# openevse-ac-filter-v1_1.net
KiCad netlist of a schematic drawn in EAGLE
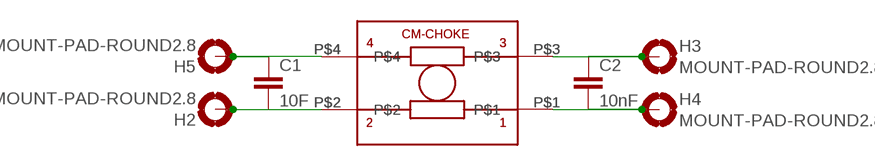
[diagram p0: schematic, sheet 1]

(export (version "E")
  (design (tool "Eeschema 10.0.6"))
  (components
    (comp (ref "C1")
      (value "10F")
      (footprint "eagle-import:C5B2.5")
      (libsource (lib "eagle-import") (part "C5/2.5"))
    )
    (comp (ref "C2")
      (value "10nF")
      (footprint "eagle-import:C5B2.5")
      (libsource (lib "eagle-import") (part "C5/2.5"))
    )
    (comp (ref "H2")
      (value "MOUNT-PAD-ROUND2.8")
      (footprint "eagle-import:2,8-PAD")
      (libsource (lib "eagle-import") (part "MOUNT-PAD-ROUND2.8"))
    )
    (comp (ref "H3")
      (value "MOUNT-PAD-ROUND2.8")
      (footprint "eagle-import:2,8-PAD")
      (libsource (lib "eagle-import") (part "MOUNT-PAD-ROUND2.8"))
    )
    (comp (ref "H4")
      (value "MOUNT-PAD-ROUND2.8")
      (footprint "eagle-import:2,8-PAD")
      (libsource (lib "eagle-import") (part "MOUNT-PAD-ROUND2.8"))
    )
    (comp (ref "H5")
      (value "MOUNT-PAD-ROUND2.8")
      (footprint "eagle-import:2,8-PAD")
      (libsource (lib "eagle-import") (part "MOUNT-PAD-ROUND2.8"))
    )
    (comp (ref "U$1")
      (value "47mH")
      (footprint "eagle-import:RN114-0.3-02-47M")
      (libsource (lib "eagle-import") (part "RN114-0.3-02-47M"))
    )
    (comp (ref "U$2")
      (value "RN214-0.3-02-47M")
      (footprint "eagle-import:RN214-0.3-02-47M")
      (libsource (lib "eagle-import") (part "RN214-0.3-02-47M"))
    )
  )
  (nets
    (net (code "1") (name "Net-(H2-MOUNT)") (class "Default")
      (node (ref "C1") (pin "2") (pinfunction "2_2") (pintype "passive"))
      (node (ref "H2") (pin "B2,8") (pinfunction "MOUNT_B2,8") (pintype "passive"))
      (node (ref "U$1") (pin "P$2") (pinfunction "P$2_P$2") (pintype "bidirectional"))
      (node (ref "U$2") (pin "P$2") (pinfunction "P$2_P$2") (pintype "bidirectional"))
    )
    (net (code "2") (name "Net-(H3-MOUNT)") (class "Default")
      (node (ref "C2") (pin "1") (pinfunction "1_1") (pintype "passive"))
      (node (ref "H3") (pin "B2,8") (pinfunction "MOUNT_B2,8") (pintype "passive"))
      (node (ref "U$1") (pin "P$3") (pinfunction "P$3_P$3") (pintype "bidirectional"))
      (node (ref "U$2") (pin "P$3") (pinfunction "P$3_P$3") (pintype "bidirectional"))
    )
    (net (code "3") (name "Net-(H4-MOUNT)") (class "Default")
      (node (ref "C2") (pin "2") (pinfunction "2_2") (pintype "passive"))
      (node (ref "H4") (pin "B2,8") (pinfunction "MOUNT_B2,8") (pintype "passive"))
      (node (ref "U$1") (pin "P$1") (pinfunction "P$1_P$1") (pintype "bidirectional"))
      (node (ref "U$2") (pin "P$1") (pinfunction "P$1_P$1") (pintype "bidirectional"))
    )
    (net (code "4") (name "Net-(H5-MOUNT)") (class "Default")
      (node (ref "C1") (pin "1") (pinfunction "1_1") (pintype "passive"))
      (node (ref "H5") (pin "B2,8") (pinfunction "MOUNT_B2,8") (pintype "passive"))
      (node (ref "U$1") (pin "P$4") (pinfunction "P$4_P$4") (pintype "bidirectional"))
      (node (ref "U$2") (pin "P$4") (pinfunction "P$4_P$4") (pintype "bidirectional"))
    )
  )
)
